# PainRegister_Amplifier.net
KiCad netlist of a schematic drawn in Altium Designer
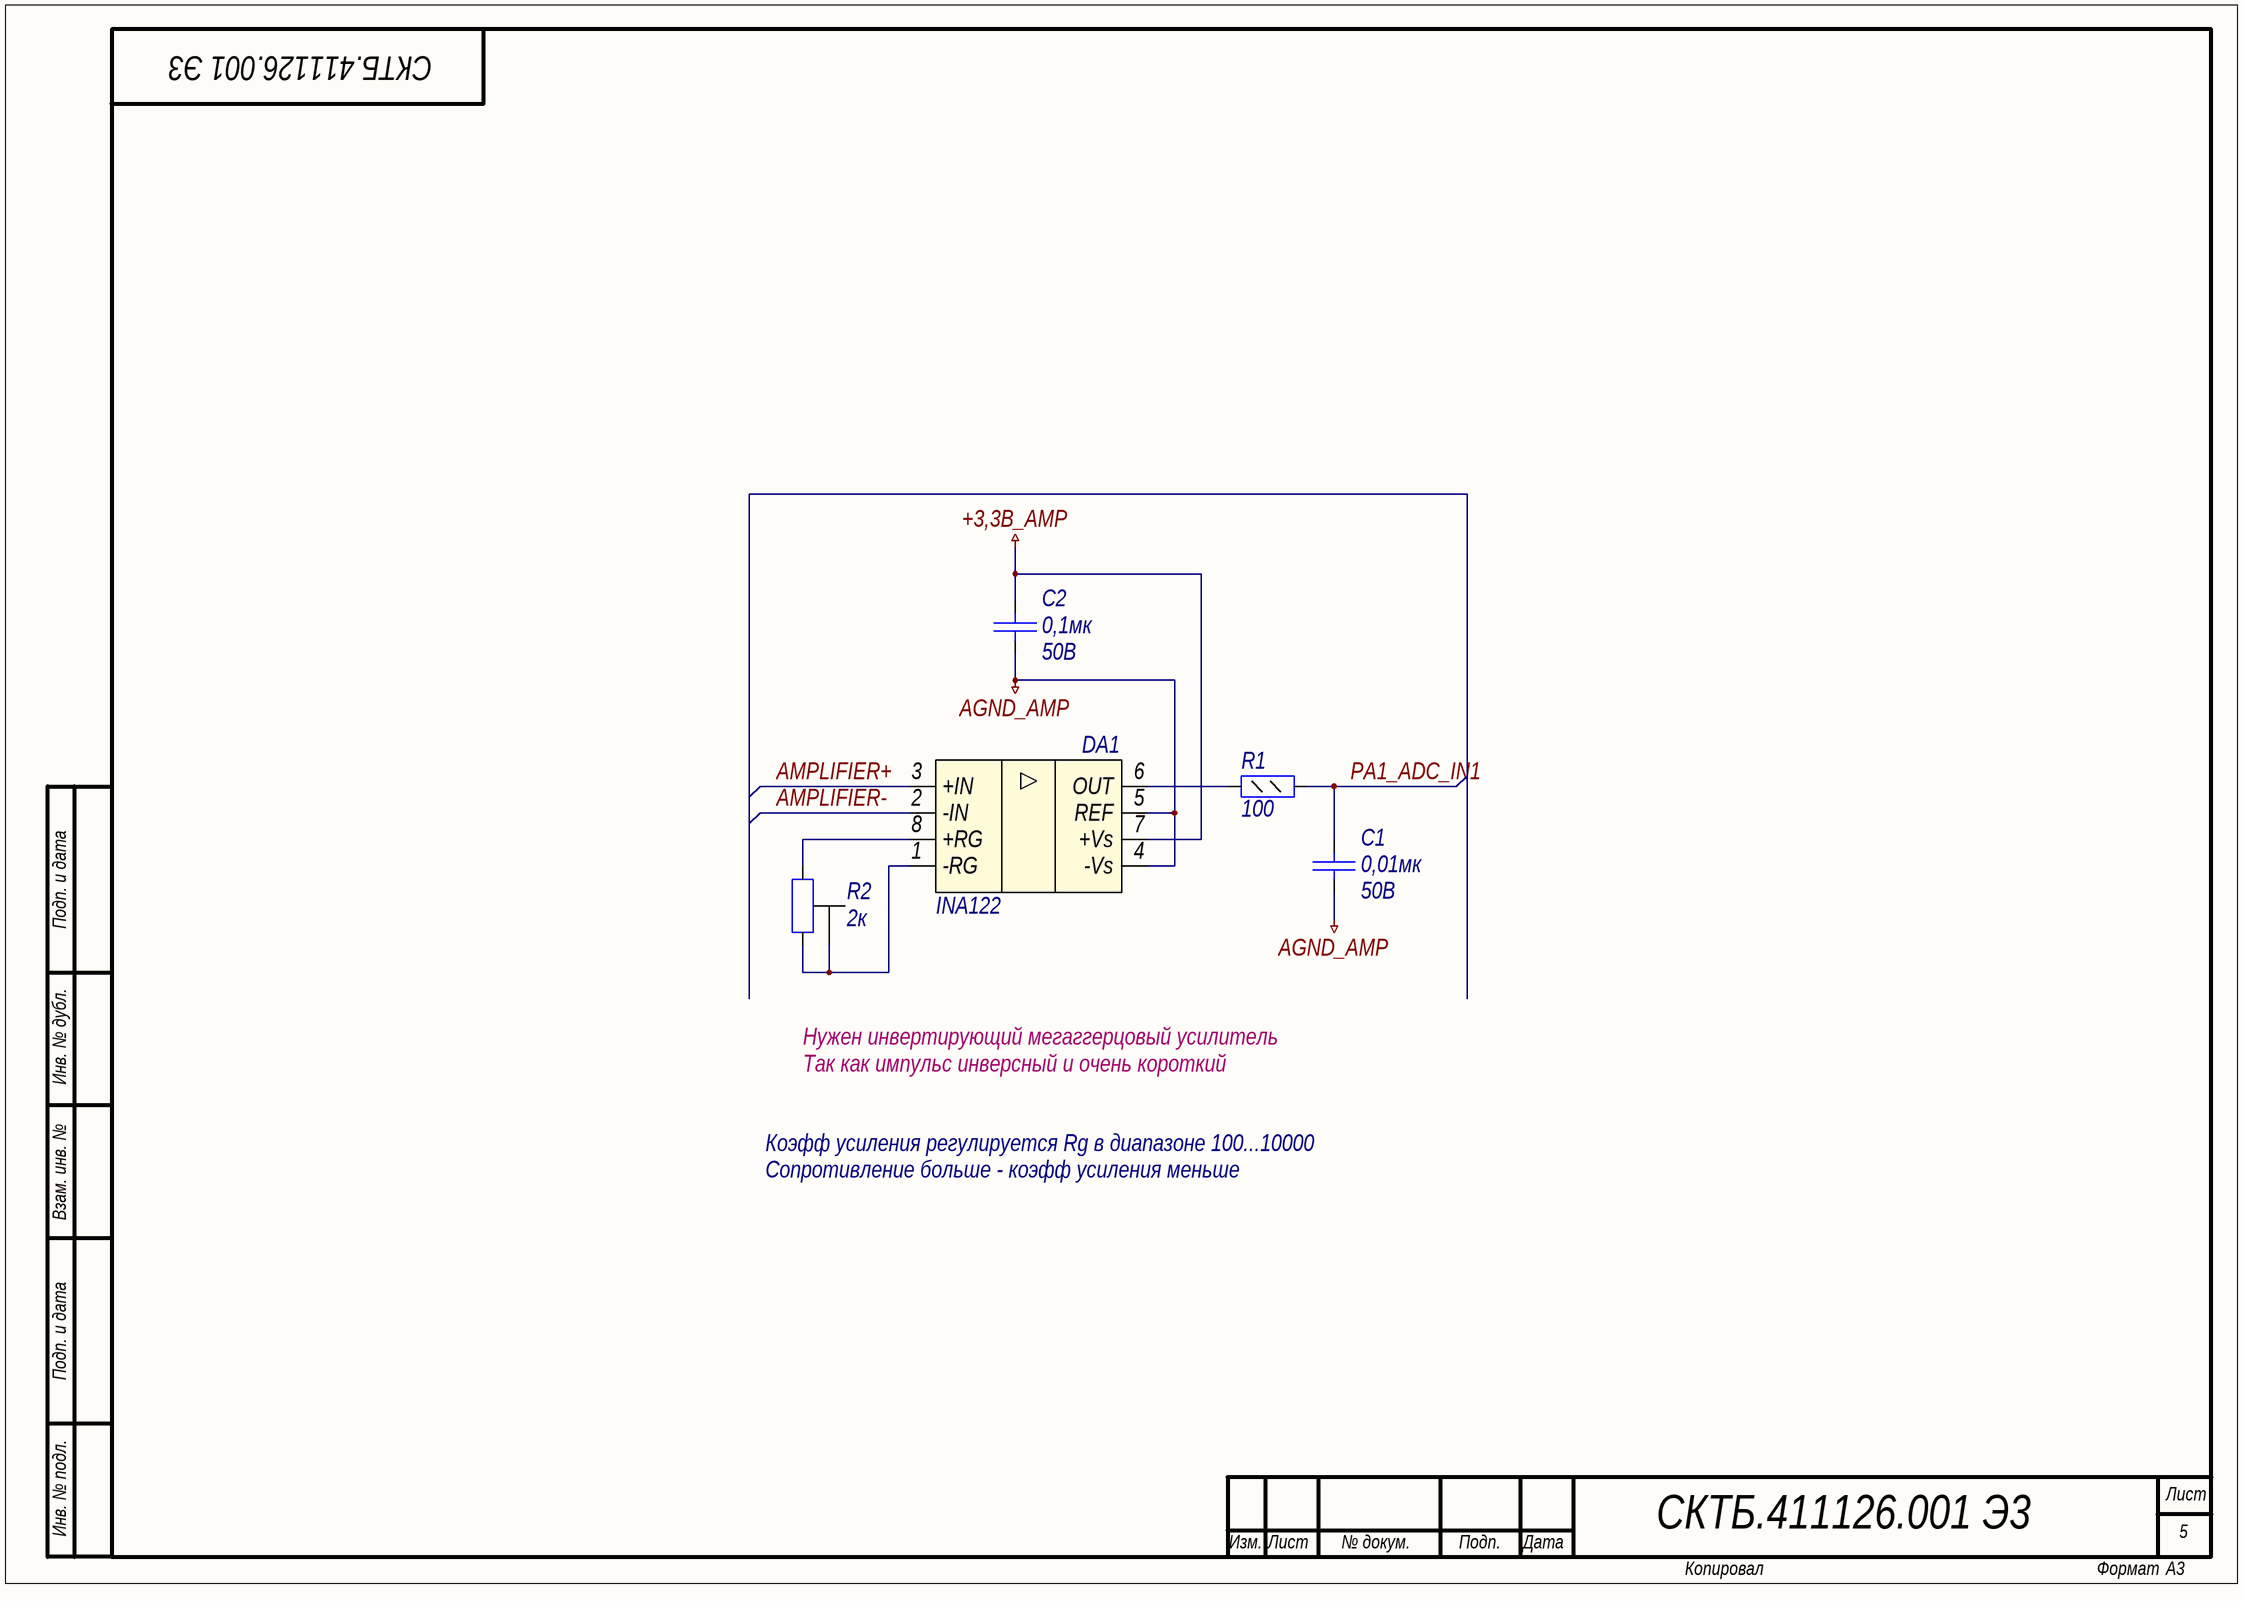
[diagram p0: PainRegister_Amplifier.SchDoc]

(export (version "E")
  (design (tool "Eeschema 10.0.6"))
  (components
    (comp (ref "C1")
      (value "0,01мк")
      (footprint "C0805")
      (description "Конденсатор")
      (fields
        (field (name "VOLTAGE") "50B")
        (field (name "PART NUMBER") "GRM216R71H103K")
        (field (name "Comment") "Capacitor")
      )
      (libsource (lib "MOP44") (part "Capacitor"))
    )
    (comp (ref "C2")
      (value "0,1мк")
      (footprint "C0805")
      (description "Конденсатор")
      (fields
        (field (name "VOLTAGE") "50В")
        (field (name "PART NUMBER") "GRM21BR71H104KA01L ")
        (field (name "Comment") "Capacitor")
      )
      (libsource (lib "MOP44") (part "Capacitor"))
    )
    (comp (ref "DA1")
      (value "INA122")
      (footprint "SO8")
      (description "Low Cost Low Power  Instrumentation Amplifier")
      (fields (field (name "PART NUMBER") "INA122PU"))
      (libsource (lib "MOP44") (part "INA122"))
    )
    (comp (ref "R1")
      (value "100")
      (footprint "R0805")
      (description "Резистор")
      (fields (field (name "PART NUMBER") "RC0805FR-07100RL") (field (name "POWER") "0,125Вт"))
      (libsource (lib "MOP44") (part "Resistor_0,125Вт"))
    )
    (comp (ref "R2")
      (value "2к")
      (footprint "3296Y")
      (description "Potentiometer")
      (fields (field (name "PART NUMBER") "3296Y-1-202LF") (field (name "POWER") "0,5Вт"))
      (libsource (lib "MOP44") (part "Potentiometer"))
    )
  )
  (nets
    (net (code "1") (name "+3,3В_AMP") (class "Default")
      (node (ref "C2") (pin "2") (pinfunction "2_2") (pintype "passive"))
      (node (ref "DA1") (pin "7") (pinfunction "+Vs_7") (pintype "passive"))
    )
    (net (code "2") (name "/AMPLIFIER+") (class "Default")
      (node (ref "DA1") (pin "3") (pinfunction "+IN_3") (pintype "passive"))
    )
    (net (code "3") (name "/AMPLIFIER-") (class "Default")
      (node (ref "DA1") (pin "2") (pinfunction "-IN_2") (pintype "passive"))
    )
    (net (code "4") (name "/PA1_ADC_IN1") (class "Default")
      (node (ref "C1") (pin "2") (pinfunction "2_2") (pintype "passive"))
      (node (ref "R1") (pin "2") (pinfunction "2_2") (pintype "passive"))
    )
    (net (code "5") (name "AGND_AMP") (class "Default")
      (node (ref "C1") (pin "1") (pinfunction "1_1") (pintype "passive"))
      (node (ref "C2") (pin "1") (pinfunction "1_1") (pintype "passive"))
      (node (ref "DA1") (pin "4") (pinfunction "-Vs_4") (pintype "passive"))
      (node (ref "DA1") (pin "5") (pinfunction "REF_5") (pintype "passive"))
    )
    (net (code "6") (name "Net-(DA1-+RG)") (class "Default")
      (node (ref "DA1") (pin "8") (pinfunction "+RG_8") (pintype "passive"))
      (node (ref "R2") (pin "1") (pinfunction "1_1") (pintype "passive"))
    )
    (net (code "7") (name "Net-(DA1--RG)") (class "Default")
      (node (ref "DA1") (pin "1") (pinfunction "-RG_1") (pintype "passive"))
      (node (ref "R2") (pin "2") (pinfunction "2_2") (pintype "passive"))
      (node (ref "R2") (pin "3") (pinfunction "3_3") (pintype "passive"))
    )
    (net (code "8") (name "Net-(DA1-OUT)") (class "Default")
      (node (ref "DA1") (pin "6") (pinfunction "OUT_6") (pintype "passive"))
      (node (ref "R1") (pin "1") (pinfunction "1_1") (pintype "passive"))
    )
  )
)
